# MoteinoMegaGPSSheild.net
KiCad netlist of a schematic drawn in EAGLE
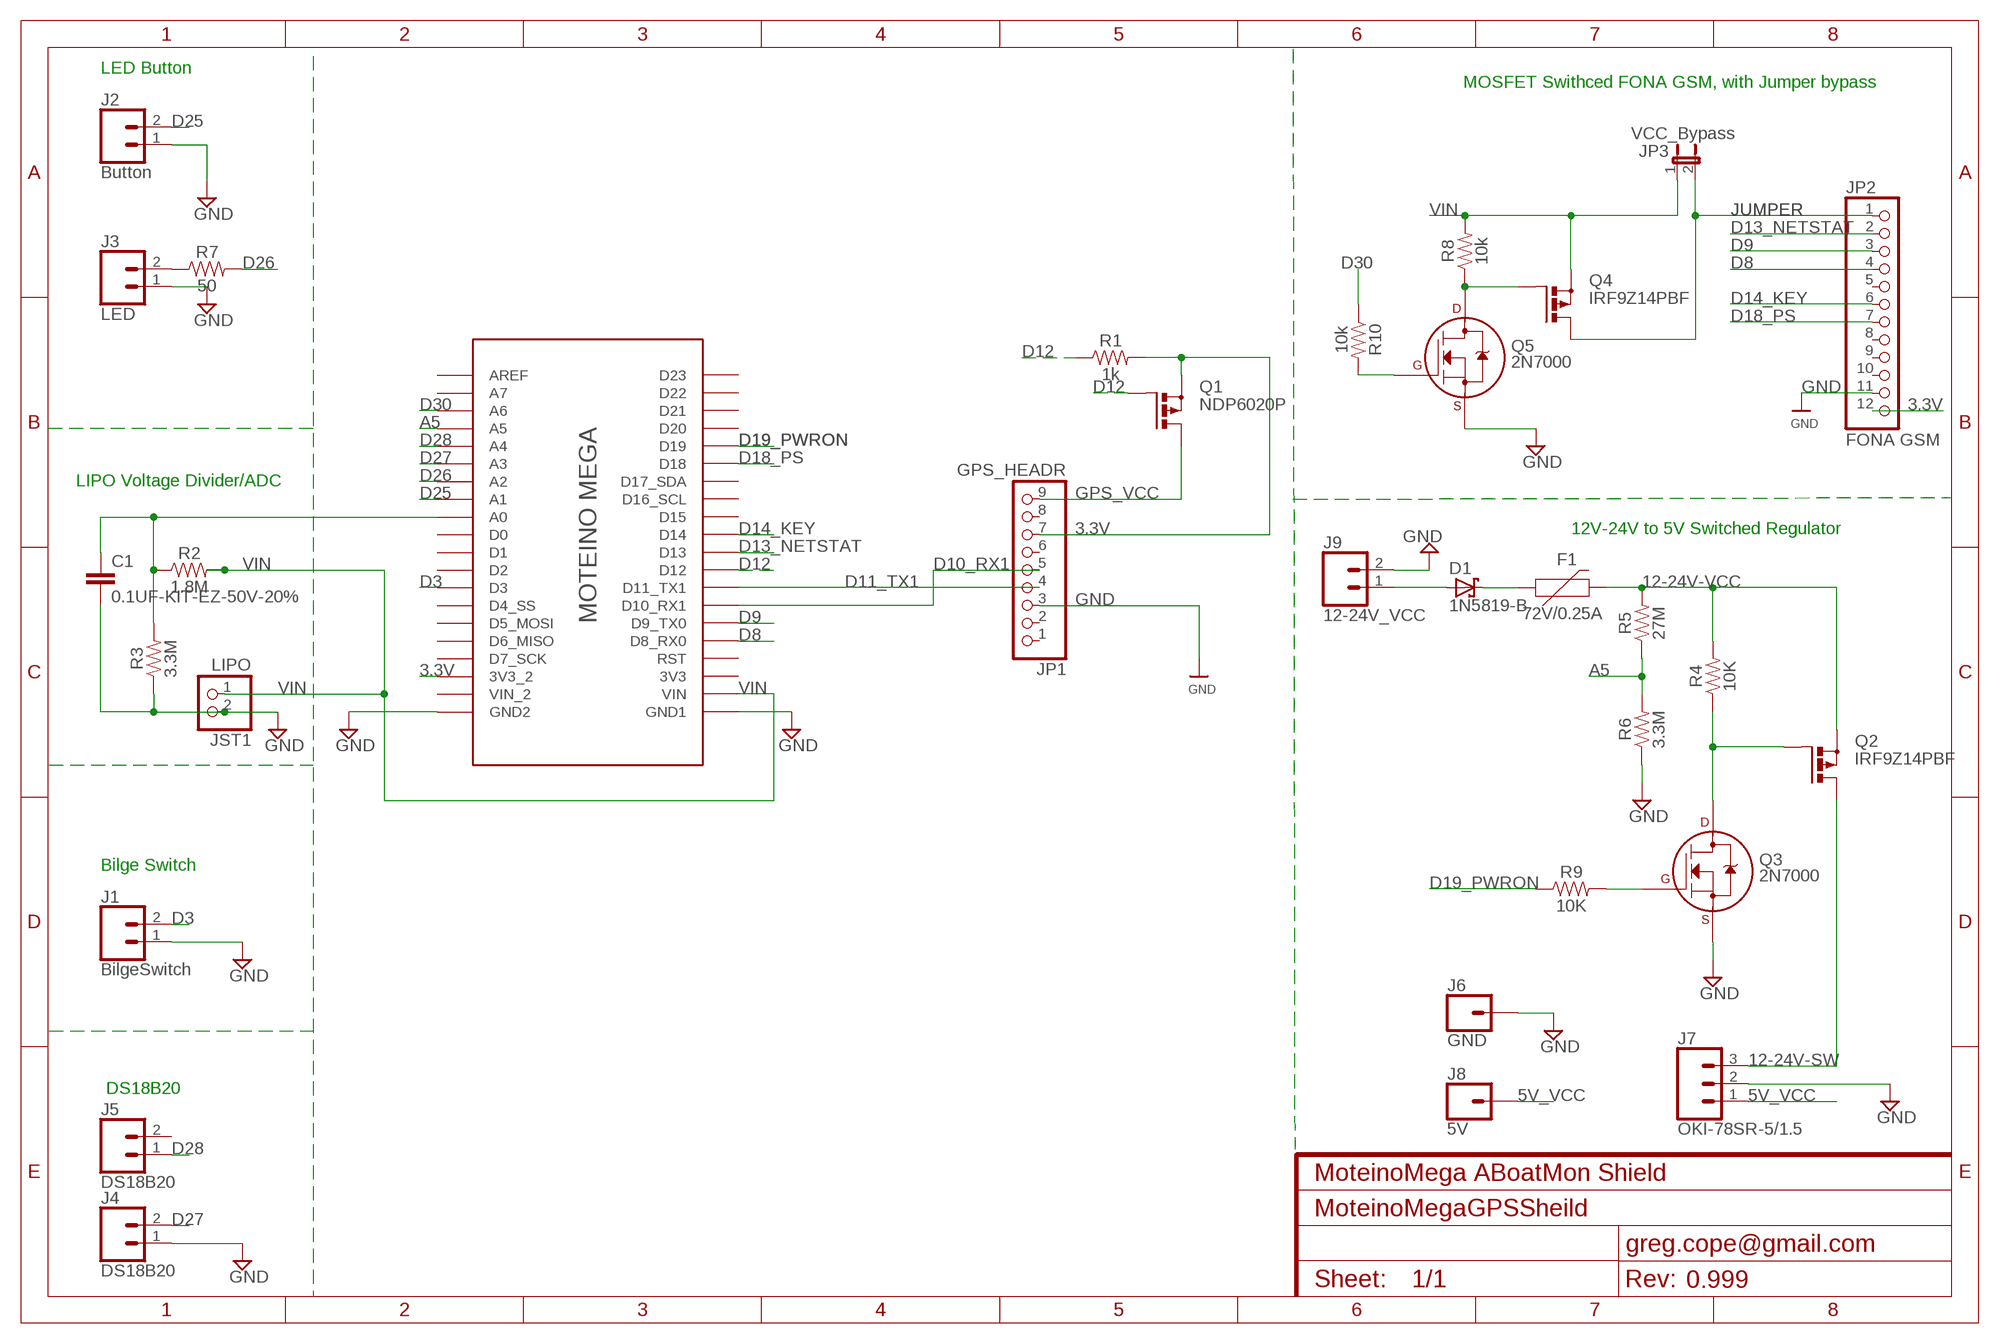
[diagram p0: schematic, sheet 1]

(export (version "E")
  (design (tool "Eeschema 10.0.6"))
  (components
    (comp (ref "C1")
      (value "0.1UF-KIT-EZ-50V-20%")
      (footprint "eagle-import:CAP-PTH-SMALL-KIT")
      (libsource (lib "eagle-import") (part "0.1UF-KIT-EZ-50V-20%"))
    )
    (comp (ref "D1")
      (value "1N5819-B")
      (footprint "eagle-import:DO41-7.6")
      (libsource (lib "eagle-import") (part "1N5819-B"))
    )
    (comp (ref "F1")
      (value "72V/0.25A")
      (footprint "eagle-import:PTH")
      (libsource (lib "eagle-import") (part "PPTC_PTH"))
    )
    (comp (ref "J1")
      (value "BilgeSwitch")
      (footprint "eagle-import:SCREWTERMINAL-3.5MM-2-NS")
      (libsource (lib "eagle-import") (part "CONN_023.5MM-NO_SILK"))
    )
    (comp (ref "J2")
      (value "Button")
      (footprint "eagle-import:SCREWTERMINAL-3.5MM-2-NS")
      (libsource (lib "eagle-import") (part "CONN_023.5MM-NO_SILK"))
    )
    (comp (ref "J3")
      (value "LED")
      (footprint "eagle-import:SCREWTERMINAL-3.5MM-2-NS")
      (libsource (lib "eagle-import") (part "CONN_023.5MM-NO_SILK"))
    )
    (comp (ref "J4")
      (value "DS18B20")
      (footprint "eagle-import:SCREWTERMINAL-3.5MM-2-NS")
      (libsource (lib "eagle-import") (part "CONN_023.5MM-NO_SILK"))
    )
    (comp (ref "J5")
      (value "DS18B20")
      (footprint "eagle-import:SCREWTERMINAL-3.5MM-2-NS")
      (libsource (lib "eagle-import") (part "CONN_023.5MM-NO_SILK"))
    )
    (comp (ref "J6")
      (value "GND")
      (footprint "eagle-import:1X01")
      (libsource (lib "eagle-import") (part "CONN_01"))
    )
    (comp (ref "J7")
      (value "OKI-78SR-5/1.5")
      (footprint "eagle-import:1X03")
      (libsource (lib "eagle-import") (part "CONN_03"))
    )
    (comp (ref "J8")
      (value "5V")
      (footprint "eagle-import:1X01")
      (libsource (lib "eagle-import") (part "CONN_01"))
    )
    (comp (ref "J9")
      (value "12-24V_VCC")
      (footprint "eagle-import:SCREWTERMINAL-3.5MM-2-NS")
      (libsource (lib "eagle-import") (part "CONN_023.5MM-NO_SILK"))
    )
    (comp (ref "JP1")
      (value "GPS_HEADR")
      (footprint "eagle-import:1X09_ROUND_70")
      (libsource (lib "eagle-import") (part "HEADER-1X970MIL"))
    )
    (comp (ref "JP2")
      (value "FONA GSM")
      (footprint "eagle-import:1X12-CB")
      (libsource (lib "eagle-import") (part "PINHD-1X12-CB"))
    )
    (comp (ref "JP3")
      (value "VCC_Bypass")
      (footprint "eagle-import:JP1")
      (libsource (lib "eagle-import") (part "JP1E"))
    )
    (comp (ref "JST1")
      (value "LIPO")
      (footprint "eagle-import:JST-PH-2-THM")
      (libsource (lib "eagle-import") (part "JST_2PIN-THM"))
    )
    (comp (ref "MOTEINO_MEGA")
      (value "HEADERS")
      (footprint "eagle-import:MOTEINO_MEGA_SIMPLE")
      (libsource (lib "eagle-import") (part "MOTEINO_MEGA_SIMPLE"))
    )
    (comp (ref "Q1")
      (value "NDP6020P")
      (footprint "eagle-import:TO220BV")
      (libsource (lib "eagle-import") (part "PMOSFET_PTO220BV"))
    )
    (comp (ref "Q2")
      (value "IRF9Z14PBF")
      (footprint "eagle-import:TO220BV")
      (libsource (lib "eagle-import") (part "PMOSFET_PTO220BV"))
    )
    (comp (ref "Q3")
      (value "2N7000")
      (footprint "eagle-import:TO-92")
      (libsource (lib "eagle-import") (part "2N700_TO922"))
    )
    (comp (ref "Q4")
      (value "IRF9Z14PBF")
      (footprint "eagle-import:TO220BV")
      (libsource (lib "eagle-import") (part "PMOSFET_PTO220BV"))
    )
    (comp (ref "Q5")
      (value "2N7000")
      (footprint "eagle-import:TO-92")
      (libsource (lib "eagle-import") (part "2N700_TO922"))
    )
    (comp (ref "R1")
      (value "1k")
      (footprint "eagle-import:AXIAL-0.3")
      (libsource (lib "eagle-import") (part "1KOHM-HORIZ-1/4W-1%"))
    )
    (comp (ref "R2")
      (value "1.8M")
      (footprint "eagle-import:AXIAL-0.3")
      (libsource (lib "eagle-import") (part "1KOHM-HORIZ-1/4W-1%"))
    )
    (comp (ref "R3")
      (value "3.3M")
      (footprint "eagle-import:AXIAL-0.3")
      (libsource (lib "eagle-import") (part "1KOHM-HORIZ-1/4W-1%"))
    )
    (comp (ref "R4")
      (value "10K")
      (footprint "eagle-import:AXIAL-0.3")
      (libsource (lib "eagle-import") (part "1KOHM-HORIZ-1/4W-1%"))
    )
    (comp (ref "R5")
      (value "27M")
      (footprint "eagle-import:AXIAL-0.3")
      (libsource (lib "eagle-import") (part "1KOHM-HORIZ-1/4W-1%"))
    )
    (comp (ref "R6")
      (value "3.3M")
      (footprint "eagle-import:AXIAL-0.3")
      (libsource (lib "eagle-import") (part "1KOHM-HORIZ-1/4W-1%"))
    )
    (comp (ref "R7")
      (value "50")
      (footprint "eagle-import:AXIAL-0.3")
      (libsource (lib "eagle-import") (part "1KOHM-HORIZ-1/4W-1%"))
    )
    (comp (ref "R8")
      (value "10k")
      (footprint "eagle-import:AXIAL-0.3")
      (libsource (lib "eagle-import") (part "1KOHM-HORIZ-1/4W-1%"))
    )
    (comp (ref "R9")
      (value "10K")
      (footprint "eagle-import:AXIAL-0.3")
      (libsource (lib "eagle-import") (part "1KOHM-HORIZ-1/4W-1%"))
    )
    (comp (ref "R10")
      (value "10k")
      (footprint "eagle-import:AXIAL-0.3")
      (libsource (lib "eagle-import") (part "1KOHM-HORIZ-1/4W-1%"))
    )
  )
  (nets
    (net (code "1") (name "/3.3V") (class "Default")
      (node (ref "JP1") (pin "7") (pinfunction "7_7") (pintype "passive"))
      (node (ref "JP2") (pin "12") (pinfunction "12_12") (pintype "passive"))
      (node (ref "MOTEINO_MEGA") (pin "3V3_2") (pinfunction "3V3_2_3V3_2") (pintype "bidirectional"))
      (node (ref "Q1") (pin "S") (pinfunction "S_S") (pintype "passive"))
      (node (ref "R1") (pin "P$2") (pinfunction "2_P$2") (pintype "passive"))
    )
    (net (code "2") (name "/5V_VCC") (class "Default")
      (node (ref "J7") (pin "1") (pinfunction "1_1") (pintype "passive"))
      (node (ref "J8") (pin "1") (pinfunction "1_1") (pintype "passive"))
    )
    (net (code "3") (name "/12-24V-SW") (class "Default")
      (node (ref "J7") (pin "3") (pinfunction "3_3") (pintype "passive"))
      (node (ref "Q2") (pin "D") (pinfunction "D_D") (pintype "passive"))
    )
    (net (code "4") (name "/12-24V-VCC") (class "Default")
      (node (ref "F1") (pin "P$2") (pinfunction "2_P$2") (pintype "bidirectional"))
      (node (ref "Q2") (pin "S") (pinfunction "S_S") (pintype "passive"))
      (node (ref "R4") (pin "P$2") (pinfunction "2_P$2") (pintype "passive"))
      (node (ref "R5") (pin "P$2") (pinfunction "2_P$2") (pintype "passive"))
    )
    (net (code "5") (name "/A5") (class "Default")
      (node (ref "MOTEINO_MEGA") (pin "A5") (pinfunction "A5_A5") (pintype "bidirectional"))
      (node (ref "R5") (pin "P$1") (pinfunction "1_P$1") (pintype "passive"))
      (node (ref "R6") (pin "P$2") (pinfunction "2_P$2") (pintype "passive"))
    )
    (net (code "6") (name "/D3") (class "Default")
      (node (ref "J1") (pin "2") (pinfunction "2_2") (pintype "passive"))
      (node (ref "MOTEINO_MEGA") (pin "D3") (pinfunction "D3_D3") (pintype "bidirectional"))
    )
    (net (code "7") (name "/D8") (class "Default")
      (node (ref "JP2") (pin "4") (pinfunction "4_4") (pintype "passive"))
      (node (ref "MOTEINO_MEGA") (pin "D8") (pinfunction "D8_RX0_D8") (pintype "bidirectional"))
    )
    (net (code "8") (name "/D9") (class "Default")
      (node (ref "JP2") (pin "3") (pinfunction "3_3") (pintype "passive"))
      (node (ref "MOTEINO_MEGA") (pin "D9") (pinfunction "D9_TX0_D9") (pintype "bidirectional"))
    )
    (net (code "9") (name "/D10_RX1") (class "Default")
      (node (ref "JP1") (pin "5") (pinfunction "5_5") (pintype "passive"))
      (node (ref "MOTEINO_MEGA") (pin "D10") (pinfunction "D10_RX1_D10") (pintype "bidirectional"))
    )
    (net (code "10") (name "/D11_TX1") (class "Default")
      (node (ref "JP1") (pin "4") (pinfunction "4_4") (pintype "passive"))
      (node (ref "MOTEINO_MEGA") (pin "D11") (pinfunction "D11_TX1_D11") (pintype "bidirectional"))
    )
    (net (code "11") (name "/D12") (class "Default")
      (node (ref "MOTEINO_MEGA") (pin "D12") (pinfunction "D12_D12") (pintype "bidirectional"))
      (node (ref "Q1") (pin "G") (pinfunction "G_G") (pintype "passive"))
      (node (ref "R1") (pin "P$1") (pinfunction "1_P$1") (pintype "passive"))
    )
    (net (code "12") (name "/D13_NETSTAT") (class "Default")
      (node (ref "JP2") (pin "2") (pinfunction "2_2") (pintype "passive"))
      (node (ref "MOTEINO_MEGA") (pin "D13") (pinfunction "D13_D13") (pintype "bidirectional"))
    )
    (net (code "13") (name "/D14_KEY") (class "Default")
      (node (ref "JP2") (pin "6") (pinfunction "6_6") (pintype "passive"))
      (node (ref "MOTEINO_MEGA") (pin "D14") (pinfunction "D14_D14") (pintype "bidirectional"))
    )
    (net (code "14") (name "/D18_PS") (class "Default")
      (node (ref "JP2") (pin "7") (pinfunction "7_7") (pintype "passive"))
      (node (ref "MOTEINO_MEGA") (pin "D18") (pinfunction "D18_D18") (pintype "bidirectional"))
    )
    (net (code "15") (name "/D19_PWRON") (class "Default")
      (node (ref "MOTEINO_MEGA") (pin "D19") (pinfunction "D19_D19") (pintype "bidirectional"))
      (node (ref "R9") (pin "P$1") (pinfunction "1_P$1") (pintype "passive"))
    )
    (net (code "16") (name "/D25") (class "Default")
      (node (ref "J2") (pin "2") (pinfunction "2_2") (pintype "passive"))
      (node (ref "MOTEINO_MEGA") (pin "A1") (pinfunction "A1_A1") (pintype "bidirectional"))
    )
    (net (code "17") (name "/D26") (class "Default")
      (node (ref "MOTEINO_MEGA") (pin "A2") (pinfunction "A2_A2") (pintype "bidirectional"))
      (node (ref "R7") (pin "P$2") (pinfunction "2_P$2") (pintype "passive"))
    )
    (net (code "18") (name "/D27") (class "Default")
      (node (ref "J4") (pin "2") (pinfunction "2_2") (pintype "passive"))
      (node (ref "MOTEINO_MEGA") (pin "A3") (pinfunction "A3_A3") (pintype "bidirectional"))
    )
    (net (code "19") (name "/D28") (class "Default")
      (node (ref "J5") (pin "1") (pinfunction "1_1") (pintype "passive"))
      (node (ref "MOTEINO_MEGA") (pin "A4") (pinfunction "A4_A4") (pintype "bidirectional"))
    )
    (net (code "20") (name "/D30") (class "Default")
      (node (ref "MOTEINO_MEGA") (pin "A6") (pinfunction "A6_A6") (pintype "bidirectional"))
      (node (ref "R10") (pin "P$1") (pinfunction "1_P$1") (pintype "passive"))
    )
    (net (code "21") (name "/GPS_VCC") (class "Default")
      (node (ref "JP1") (pin "9") (pinfunction "9_9") (pintype "passive"))
      (node (ref "Q1") (pin "D") (pinfunction "D_D") (pintype "passive"))
    )
    (net (code "22") (name "/JUMPER") (class "Default")
      (node (ref "JP2") (pin "1") (pinfunction "1_1") (pintype "passive"))
      (node (ref "JP3") (pin "2") (pinfunction "2_2") (pintype "passive"))
      (node (ref "Q4") (pin "D") (pinfunction "D_D") (pintype "passive"))
    )
    (net (code "25") (name "/VIN") (class "Default")
      (node (ref "JP3") (pin "1") (pinfunction "1_1") (pintype "passive"))
      (node (ref "JST1") (pin "1") (pinfunction "2_1") (pintype "passive"))
      (node (ref "MOTEINO_MEGA") (pin "VIN") (pinfunction "VIN_VIN") (pintype "bidirectional"))
      (node (ref "Q4") (pin "S") (pinfunction "S_S") (pintype "passive"))
      (node (ref "R2") (pin "P$2") (pinfunction "2_P$2") (pintype "passive"))
      (node (ref "R8") (pin "P$2") (pinfunction "2_P$2") (pintype "passive"))
    )
    (net (code "26") (name "GND") (class "Default")
      (node (ref "C1") (pin "2") (pinfunction "2_2") (pintype "passive"))
      (node (ref "J1") (pin "1") (pinfunction "1_1") (pintype "passive"))
      (node (ref "J2") (pin "1") (pinfunction "1_1") (pintype "passive"))
      (node (ref "J3") (pin "1") (pinfunction "1_1") (pintype "passive"))
      (node (ref "J4") (pin "1") (pinfunction "1_1") (pintype "passive"))
      (node (ref "J6") (pin "1") (pinfunction "1_1") (pintype "passive"))
      (node (ref "J7") (pin "2") (pinfunction "2_2") (pintype "passive"))
      (node (ref "J9") (pin "2") (pinfunction "2_2") (pintype "passive"))
      (node (ref "JP1") (pin "3") (pinfunction "3_3") (pintype "passive"))
      (node (ref "JP2") (pin "11") (pinfunction "11_11") (pintype "passive"))
      (node (ref "JST1") (pin "2") (pinfunction "1_2") (pintype "passive"))
      (node (ref "MOTEINO_MEGA") (pin "GND1") (pinfunction "GND1_GND1") (pintype "bidirectional"))
      (node (ref "MOTEINO_MEGA") (pin "GND_2") (pinfunction "GND2_GND_2") (pintype "bidirectional"))
      (node (ref "Q3") (pin "1") (pinfunction "S_1") (pintype "bidirectional"))
      (node (ref "Q5") (pin "1") (pinfunction "S_1") (pintype "bidirectional"))
      (node (ref "R3") (pin "P$1") (pinfunction "1_P$1") (pintype "passive"))
      (node (ref "R6") (pin "P$1") (pinfunction "1_P$1") (pintype "passive"))
    )
    (net (code "27") (name "Net-(D1-PadA)") (class "Default")
      (node (ref "D1") (pin "A") (pinfunction "A_A") (pintype "passive"))
      (node (ref "J9") (pin "1") (pinfunction "1_1") (pintype "passive"))
    )
    (net (code "28") (name "Net-(F1-1)") (class "Default")
      (node (ref "D1") (pin "C") (pinfunction "C_C") (pintype "passive"))
      (node (ref "F1") (pin "P$1") (pinfunction "1_P$1") (pintype "bidirectional"))
    )
    (net (code "29") (name "Net-(Q3-D)") (class "Default")
      (node (ref "Q2") (pin "G") (pinfunction "G_G") (pintype "passive"))
      (node (ref "Q3") (pin "3") (pinfunction "D_3") (pintype "bidirectional"))
      (node (ref "R4") (pin "P$1") (pinfunction "1_P$1") (pintype "passive"))
    )
    (net (code "30") (name "Net-(Q3-G)") (class "Default")
      (node (ref "Q3") (pin "2") (pinfunction "G_2") (pintype "tri_state"))
      (node (ref "R9") (pin "P$2") (pinfunction "2_P$2") (pintype "passive"))
    )
    (net (code "31") (name "Net-(Q5-D)") (class "Default")
      (node (ref "Q4") (pin "G") (pinfunction "G_G") (pintype "passive"))
      (node (ref "Q5") (pin "3") (pinfunction "D_3") (pintype "bidirectional"))
      (node (ref "R8") (pin "P$1") (pinfunction "1_P$1") (pintype "passive"))
    )
    (net (code "32") (name "Net-(Q5-G)") (class "Default")
      (node (ref "Q5") (pin "2") (pinfunction "G_2") (pintype "tri_state"))
      (node (ref "R10") (pin "P$2") (pinfunction "2_P$2") (pintype "passive"))
    )
    (net (code "33") (name "Net-(R2-1)") (class "Default")
      (node (ref "C1") (pin "1") (pinfunction "1_1") (pintype "passive"))
      (node (ref "MOTEINO_MEGA") (pin "A0") (pinfunction "A0_A0") (pintype "bidirectional"))
      (node (ref "R2") (pin "P$1") (pinfunction "1_P$1") (pintype "passive"))
      (node (ref "R3") (pin "P$2") (pinfunction "2_P$2") (pintype "passive"))
    )
    (net (code "34") (name "Net-(R7-1)") (class "Default")
      (node (ref "J3") (pin "2") (pinfunction "2_2") (pintype "passive"))
      (node (ref "R7") (pin "P$1") (pinfunction "1_P$1") (pintype "passive"))
    )
    (net (code "35") (name "unconnected-(J5-Pad2)") (class "Default")
      (node (ref "J5") (pin "2") (pinfunction "2_2") (pintype "passive"))
    )
    (net (code "36") (name "unconnected-(JP1-Pad1)") (class "Default")
      (node (ref "JP1") (pin "1") (pinfunction "1_1") (pintype "passive"))
    )
    (net (code "37") (name "unconnected-(JP1-Pad2)") (class "Default")
      (node (ref "JP1") (pin "2") (pinfunction "2_2") (pintype "passive"))
    )
    (net (code "38") (name "unconnected-(JP1-Pad6)") (class "Default")
      (node (ref "JP1") (pin "6") (pinfunction "6_6") (pintype "passive"))
    )
    (net (code "39") (name "unconnected-(JP1-Pad8)") (class "Default")
      (node (ref "JP1") (pin "8") (pinfunction "8_8") (pintype "passive"))
    )
    (net (code "40") (name "unconnected-(JP2-Pad5)") (class "Default")
      (node (ref "JP2") (pin "5") (pinfunction "5_5") (pintype "passive"))
    )
    (net (code "41") (name "unconnected-(JP2-Pad8)") (class "Default")
      (node (ref "JP2") (pin "8") (pinfunction "8_8") (pintype "passive"))
    )
    (net (code "42") (name "unconnected-(JP2-Pad9)") (class "Default")
      (node (ref "JP2") (pin "9") (pinfunction "9_9") (pintype "passive"))
    )
    (net (code "43") (name "unconnected-(JP2-Pad10)") (class "Default")
      (node (ref "JP2") (pin "10") (pinfunction "10_10") (pintype "passive"))
    )
    (net (code "44") (name "unconnected-(MOTEINO_MEGA-D4_SS-PadD4)") (class "Default")
      (node (ref "MOTEINO_MEGA") (pin "D4") (pinfunction "D4_SS_D4") (pintype "bidirectional"))
    )
    (net (code "45") (name "unconnected-(MOTEINO_MEGA-D5_MOSI-PadD5)") (class "Default")
      (node (ref "MOTEINO_MEGA") (pin "D5") (pinfunction "D5_MOSI_D5") (pintype "bidirectional"))
    )
    (net (code "46") (name "unconnected-(MOTEINO_MEGA-D6_MISO-PadD6)") (class "Default")
      (node (ref "MOTEINO_MEGA") (pin "D6") (pinfunction "D6_MISO_D6") (pintype "bidirectional"))
    )
    (net (code "47") (name "unconnected-(MOTEINO_MEGA-D7_SCK-PadD7)") (class "Default")
      (node (ref "MOTEINO_MEGA") (pin "D7") (pinfunction "D7_SCK_D7") (pintype "bidirectional"))
    )
    (net (code "48") (name "unconnected-(MOTEINO_MEGA-D16_SCL-PadD16)") (class "Default")
      (node (ref "MOTEINO_MEGA") (pin "D16") (pinfunction "D16_SCL_D16") (pintype "bidirectional"))
    )
    (net (code "49") (name "unconnected-(MOTEINO_MEGA-D17_SDA-PadD17)") (class "Default")
      (node (ref "MOTEINO_MEGA") (pin "D17") (pinfunction "D17_SDA_D17") (pintype "bidirectional"))
    )
    (net (code "50") (name "unconnected-(MOTEINO_MEGA-Pad3V3)") (class "Default")
      (node (ref "MOTEINO_MEGA") (pin "3V3") (pinfunction "3V3_3V3") (pintype "bidirectional"))
    )
    (net (code "51") (name "unconnected-(MOTEINO_MEGA-PadA7)") (class "Default")
      (node (ref "MOTEINO_MEGA") (pin "A7") (pinfunction "A7_A7") (pintype "bidirectional"))
    )
    (net (code "52") (name "unconnected-(MOTEINO_MEGA-PadAREF)") (class "Default")
      (node (ref "MOTEINO_MEGA") (pin "AREF") (pinfunction "AREF_AREF") (pintype "bidirectional"))
    )
    (net (code "53") (name "unconnected-(MOTEINO_MEGA-PadD0)") (class "Default")
      (node (ref "MOTEINO_MEGA") (pin "D0") (pinfunction "D0_D0") (pintype "bidirectional"))
    )
    (net (code "54") (name "unconnected-(MOTEINO_MEGA-PadD1)") (class "Default")
      (node (ref "MOTEINO_MEGA") (pin "D1") (pinfunction "D1_D1") (pintype "bidirectional"))
    )
    (net (code "55") (name "unconnected-(MOTEINO_MEGA-PadD2)") (class "Default")
      (node (ref "MOTEINO_MEGA") (pin "D2") (pinfunction "D2_D2") (pintype "bidirectional"))
    )
    (net (code "56") (name "unconnected-(MOTEINO_MEGA-PadD15)") (class "Default")
      (node (ref "MOTEINO_MEGA") (pin "D15") (pinfunction "D15_D15") (pintype "bidirectional"))
    )
    (net (code "57") (name "unconnected-(MOTEINO_MEGA-PadD20)") (class "Default")
      (node (ref "MOTEINO_MEGA") (pin "D20") (pinfunction "D20_D20") (pintype "bidirectional"))
    )
    (net (code "58") (name "unconnected-(MOTEINO_MEGA-PadD21)") (class "Default")
      (node (ref "MOTEINO_MEGA") (pin "D21") (pinfunction "D21_D21") (pintype "bidirectional"))
    )
    (net (code "59") (name "unconnected-(MOTEINO_MEGA-PadD22)") (class "Default")
      (node (ref "MOTEINO_MEGA") (pin "D22") (pinfunction "D22_D22") (pintype "bidirectional"))
    )
    (net (code "60") (name "unconnected-(MOTEINO_MEGA-PadD23)") (class "Default")
      (node (ref "MOTEINO_MEGA") (pin "D23") (pinfunction "D23_D23") (pintype "bidirectional"))
    )
    (net (code "61") (name "unconnected-(MOTEINO_MEGA-PadRST)") (class "Default")
      (node (ref "MOTEINO_MEGA") (pin "RST") (pinfunction "RST_RST") (pintype "bidirectional"))
    )
    (net (code "62") (name "unconnected-(MOTEINO_MEGA-PadVIN_2)") (class "Default")
      (node (ref "MOTEINO_MEGA") (pin "VIN_2") (pinfunction "VIN_2_VIN_2") (pintype "bidirectional"))
    )
  )
)
